# TSAL_contactor_state_and_accumulator_vol.net
KiCad netlist of a schematic drawn in EAGLE
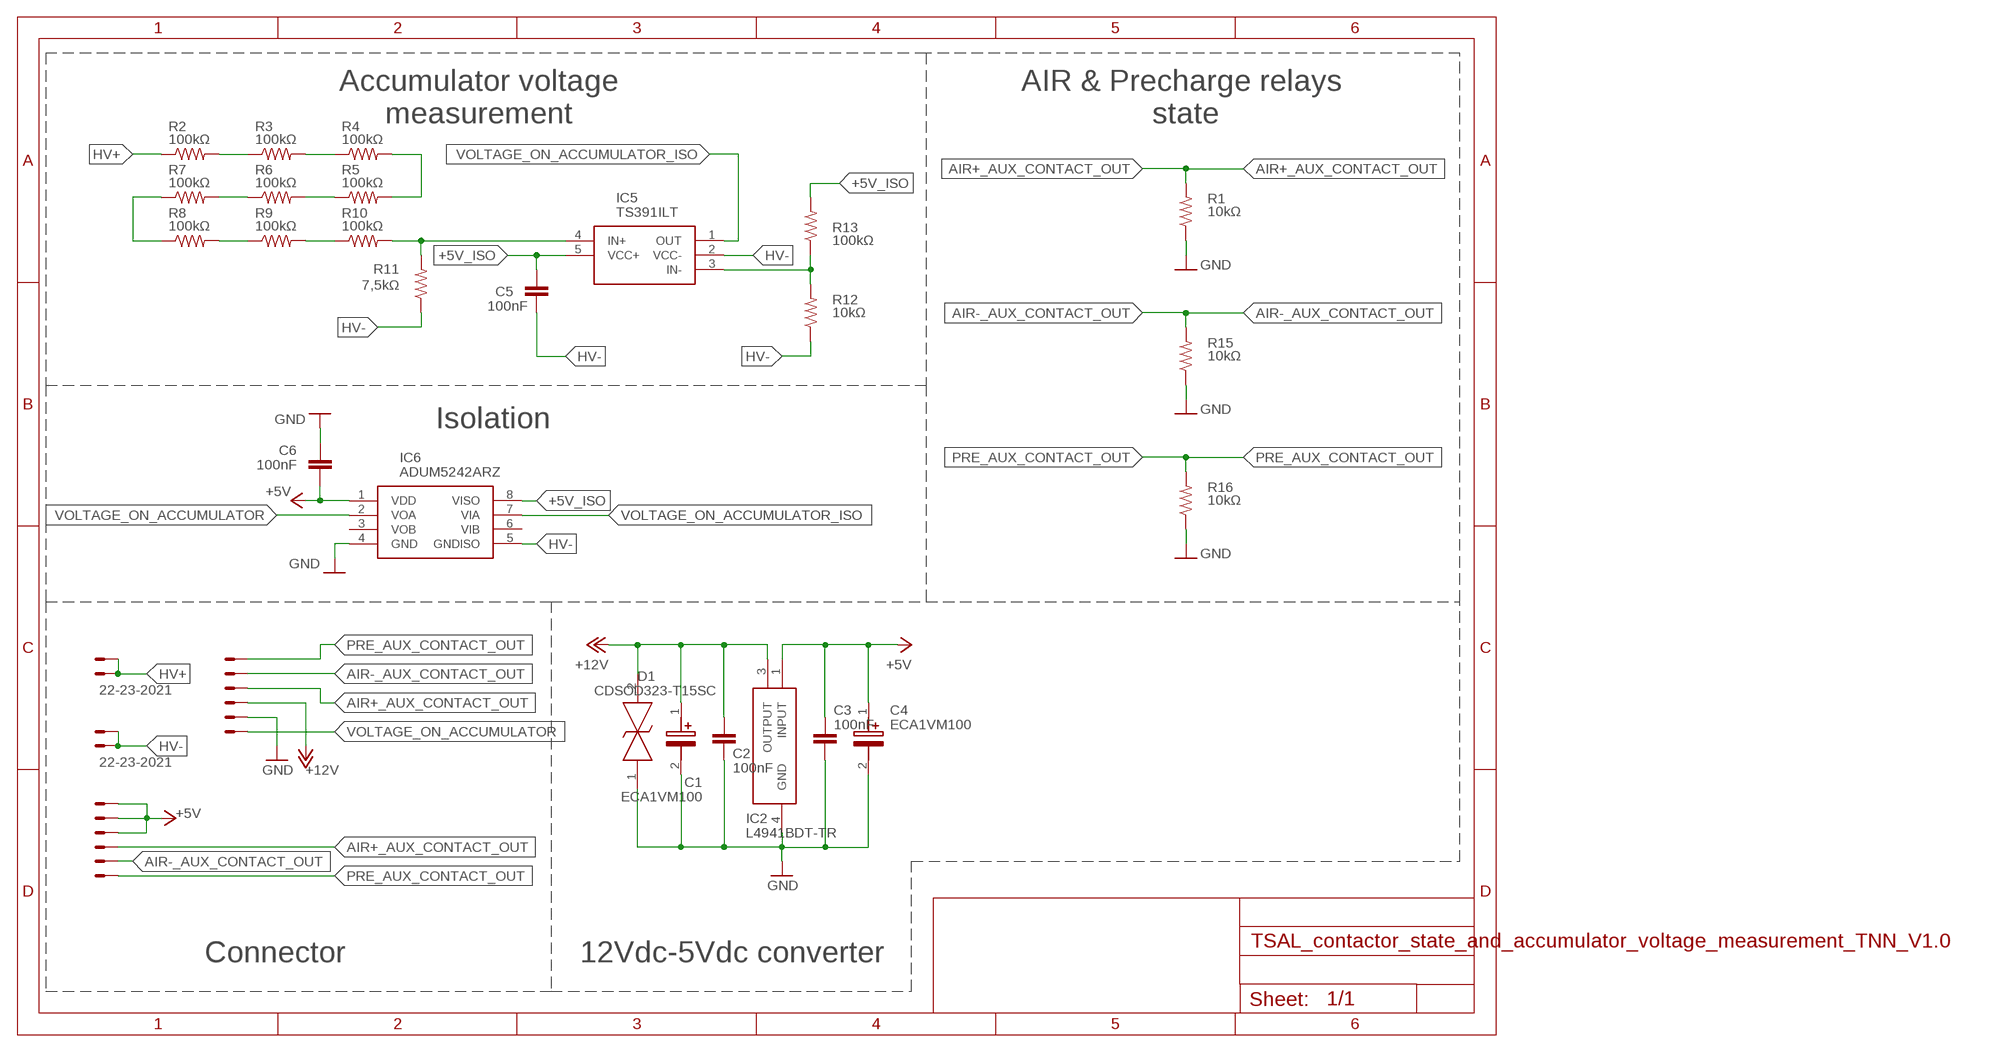
[diagram p0: schematic, sheet 1]

(export (version "E")
  (design (tool "Eeschema 10.0.6"))
  (components
    (comp (ref "AUX_CONTACT")
      (value "22-23-2061")
      (footprint "eagle-import:22-23-2061")
      (fields (field (name "MF") "MOLEX"))
      (libsource (lib "eagle-import") (part "22-23-2061"))
    )
    (comp (ref "C1")
      (value "ECA1VM100")
      (footprint "eagle-import:CAPPRD200W55D525H1200")
      (libsource (lib "eagle-import") (part "ECA1VM100"))
    )
    (comp (ref "C2")
      (value "100nF")
      (footprint "eagle-import:C0603")
      (libsource (lib "eagle-import") (part "C-EUC0603"))
    )
    (comp (ref "C3")
      (value "100nF")
      (footprint "eagle-import:C0603")
      (libsource (lib "eagle-import") (part "C-EUC0603"))
    )
    (comp (ref "C4")
      (value "ECA1VM100")
      (footprint "eagle-import:CAPPRD200W55D525H1200")
      (libsource (lib "eagle-import") (part "ECA1VM100"))
    )
    (comp (ref "C5")
      (value "100nF")
      (footprint "eagle-import:C0603")
      (libsource (lib "eagle-import") (part "C-EUC0603"))
    )
    (comp (ref "C6")
      (value "100nF")
      (footprint "eagle-import:C0603")
      (libsource (lib "eagle-import") (part "C-EUC0603"))
    )
    (comp (ref "D1")
      (value "CDSOD323-T15SC")
      (footprint "eagle-import:SOD-323")
      (fields (field (name "MOUSER_PART_NUMBER") "652-CDSOD323-T15SC"))
      (libsource (lib "eagle-import") (part "CDSOD323-T15SC"))
    )
    (comp (ref "HV+")
      (value "22-23-2021")
      (footprint "eagle-import:22-23-2021")
      (fields (field (name "MF") "MOLEX"))
      (libsource (lib "eagle-import") (part "22-23-2021"))
    )
    (comp (ref "HV-")
      (value "22-23-2021")
      (footprint "eagle-import:22-23-2021")
      (fields (field (name "MF") "MOLEX"))
      (libsource (lib "eagle-import") (part "22-23-2021"))
    )
    (comp (ref "IC2")
      (value "L4941BDT-TR")
      (footprint "eagle-import:TO228P972X240-3N")
      (fields (field (name "MOUSER_PART_NUMBER") "511-L4941BDT-TR"))
      (libsource (lib "eagle-import") (part "L4941BDT-TR"))
    )
    (comp (ref "IC5")
      (value "TS391ILT")
      (footprint "eagle-import:SOT95P280X145-5N")
      (fields (field (name "MOUSER_PART_NUMBER") "511-TS391IL"))
      (libsource (lib "eagle-import") (part "TS391ILT"))
    )
    (comp (ref "IC6")
      (value "ADUM5242ARZ")
      (footprint "eagle-import:SOIC127P600X175-8N")
      (fields (field (name "MOUSER_PART_NUMBER") "584-ADUM5242ARZ"))
      (libsource (lib "eagle-import") (part "ADUM5242ARZ"))
    )
    (comp (ref "POWER_AND_TSAL_SIGNAL")
      (value "22-23-2061")
      (footprint "eagle-import:22-23-2061")
      (fields (field (name "MF") "MOLEX"))
      (libsource (lib "eagle-import") (part "22-23-2061"))
    )
    (comp (ref "R1")
      (value "10kΩ")
      (footprint "eagle-import:R0603")
      (libsource (lib "eagle-import") (part "R-US_R0603"))
    )
    (comp (ref "R2")
      (value "100kΩ")
      (footprint "eagle-import:R0603")
      (libsource (lib "eagle-import") (part "R-US_R0603"))
    )
    (comp (ref "R3")
      (value "100kΩ")
      (footprint "eagle-import:R0603")
      (libsource (lib "eagle-import") (part "R-US_R0603"))
    )
    (comp (ref "R4")
      (value "100kΩ")
      (footprint "eagle-import:R0603")
      (libsource (lib "eagle-import") (part "R-US_R0603"))
    )
    (comp (ref "R5")
      (value "100kΩ")
      (footprint "eagle-import:R0603")
      (libsource (lib "eagle-import") (part "R-US_R0603"))
    )
    (comp (ref "R6")
      (value "100kΩ")
      (footprint "eagle-import:R0603")
      (libsource (lib "eagle-import") (part "R-US_R0603"))
    )
    (comp (ref "R7")
      (value "100kΩ")
      (footprint "eagle-import:R0603")
      (libsource (lib "eagle-import") (part "R-US_R0603"))
    )
    (comp (ref "R8")
      (value "100kΩ")
      (footprint "eagle-import:R0603")
      (libsource (lib "eagle-import") (part "R-US_R0603"))
    )
    (comp (ref "R9")
      (value "100kΩ")
      (footprint "eagle-import:R0603")
      (libsource (lib "eagle-import") (part "R-US_R0603"))
    )
    (comp (ref "R10")
      (value "100kΩ")
      (footprint "eagle-import:R0603")
      (libsource (lib "eagle-import") (part "R-US_R0603"))
    )
    (comp (ref "R11")
      (value "7,5kΩ")
      (footprint "eagle-import:R0603")
      (libsource (lib "eagle-import") (part "R-US_R0603"))
    )
    (comp (ref "R12")
      (value "10kΩ")
      (footprint "eagle-import:R0603")
      (libsource (lib "eagle-import") (part "R-US_R0603"))
    )
    (comp (ref "R13")
      (value "100kΩ")
      (footprint "eagle-import:R0603")
      (libsource (lib "eagle-import") (part "R-US_R0603"))
    )
    (comp (ref "R15")
      (value "10kΩ")
      (footprint "eagle-import:R0603")
      (libsource (lib "eagle-import") (part "R-US_R0603"))
    )
    (comp (ref "R16")
      (value "10kΩ")
      (footprint "eagle-import:R0603")
      (libsource (lib "eagle-import") (part "R-US_R0603"))
    )
  )
  (nets
    (net (code "1") (name "+5V") (class "Default")
      (node (ref "AUX_CONTACT") (pin "4") (pinfunction "S_4") (pintype "passive"))
      (node (ref "AUX_CONTACT") (pin "5") (pinfunction "S_5") (pintype "passive"))
      (node (ref "AUX_CONTACT") (pin "6") (pinfunction "S_6") (pintype "passive"))
      (node (ref "C3") (pin "1") (pinfunction "1_1") (pintype "passive"))
      (node (ref "C4") (pin "1") (pinfunction "+_1") (pintype "bidirectional"))
      (node (ref "C6") (pin "1") (pinfunction "1_1") (pintype "passive"))
      (node (ref "IC2") (pin "1") (pinfunction "INPUT_1") (pintype "output"))
      (node (ref "IC6") (pin "1") (pinfunction "VDD_1") (pintype "bidirectional"))
    )
    (net (code "2") (name "+5V_ISO") (class "Default")
      (node (ref "C5") (pin "2") (pinfunction "2_2") (pintype "passive"))
      (node (ref "IC5") (pin "5") (pinfunction "VCC+_5") (pintype "bidirectional"))
      (node (ref "IC6") (pin "8") (pinfunction "VISO_8") (pintype "bidirectional"))
      (node (ref "R13") (pin "2") (pinfunction "2_2") (pintype "passive"))
    )
    (net (code "3") (name "+12V") (class "Default")
      (node (ref "C1") (pin "1") (pinfunction "+_1") (pintype "bidirectional"))
      (node (ref "C2") (pin "1") (pinfunction "1_1") (pintype "passive"))
      (node (ref "D1") (pin "2") (pinfunction "2_2") (pintype "bidirectional"))
      (node (ref "IC2") (pin "3") (pinfunction "OUTPUT_3") (pintype "power_in"))
      (node (ref "POWER_AND_TSAL_SIGNAL") (pin "3") (pinfunction "S_3") (pintype "passive"))
    )
    (net (code "4") (name "AIR+_AUX_CONTACT_OUT") (class "Default")
      (node (ref "AUX_CONTACT") (pin "3") (pinfunction "S_3") (pintype "passive"))
      (node (ref "POWER_AND_TSAL_SIGNAL") (pin "4") (pinfunction "S_4") (pintype "passive"))
      (node (ref "R1") (pin "2") (pinfunction "2_2") (pintype "passive"))
    )
    (net (code "5") (name "AIR-_AUX_CONTACT_OUT") (class "Default")
      (node (ref "AUX_CONTACT") (pin "2") (pinfunction "S_2") (pintype "passive"))
      (node (ref "POWER_AND_TSAL_SIGNAL") (pin "5") (pinfunction "S_5") (pintype "passive"))
      (node (ref "R15") (pin "2") (pinfunction "2_2") (pintype "passive"))
    )
    (net (code "6") (name "GND") (class "Default")
      (node (ref "C1") (pin "2") (pinfunction "-_2") (pintype "bidirectional"))
      (node (ref "C2") (pin "2") (pinfunction "2_2") (pintype "passive"))
      (node (ref "C3") (pin "2") (pinfunction "2_2") (pintype "passive"))
      (node (ref "C4") (pin "2") (pinfunction "-_2") (pintype "bidirectional"))
      (node (ref "C6") (pin "2") (pinfunction "2_2") (pintype "passive"))
      (node (ref "D1") (pin "1") (pinfunction "1_1") (pintype "bidirectional"))
      (node (ref "IC2") (pin "4") (pinfunction "GND_4") (pintype "input"))
      (node (ref "IC6") (pin "4") (pinfunction "GND_4") (pintype "bidirectional"))
      (node (ref "POWER_AND_TSAL_SIGNAL") (pin "2") (pinfunction "S_2") (pintype "passive"))
      (node (ref "R1") (pin "1") (pinfunction "1_1") (pintype "passive"))
      (node (ref "R15") (pin "1") (pinfunction "1_1") (pintype "passive"))
      (node (ref "R16") (pin "1") (pinfunction "1_1") (pintype "passive"))
    )
    (net (code "7") (name "HV+") (class "Default")
      (node (ref "HV+") (pin "1") (pinfunction "S_1") (pintype "passive"))
      (node (ref "HV+") (pin "2") (pinfunction "S_2") (pintype "passive"))
      (node (ref "R2") (pin "1") (pinfunction "1_1") (pintype "passive"))
    )
    (net (code "8") (name "HV-") (class "Default")
      (node (ref "C5") (pin "1") (pinfunction "1_1") (pintype "passive"))
      (node (ref "HV-") (pin "1") (pinfunction "S_1") (pintype "passive"))
      (node (ref "HV-") (pin "2") (pinfunction "S_2") (pintype "passive"))
      (node (ref "IC5") (pin "2") (pinfunction "VCC-_2") (pintype "bidirectional"))
      (node (ref "IC6") (pin "5") (pinfunction "GNDISO_5") (pintype "bidirectional"))
      (node (ref "R11") (pin "1") (pinfunction "1_1") (pintype "passive"))
      (node (ref "R12") (pin "1") (pinfunction "1_1") (pintype "passive"))
    )
    (net (code "9") (name "Net-(IC5-IN+)") (class "Default")
      (node (ref "IC5") (pin "4") (pinfunction "IN+_4") (pintype "bidirectional"))
      (node (ref "R10") (pin "2") (pinfunction "2_2") (pintype "passive"))
      (node (ref "R11") (pin "2") (pinfunction "2_2") (pintype "passive"))
    )
    (net (code "10") (name "Net-(IC5-IN-)") (class "Default")
      (node (ref "IC5") (pin "3") (pinfunction "IN-_3") (pintype "bidirectional"))
      (node (ref "R12") (pin "2") (pinfunction "2_2") (pintype "passive"))
      (node (ref "R13") (pin "1") (pinfunction "1_1") (pintype "passive"))
    )
    (net (code "11") (name "Net-(R2-Pad2)") (class "Default")
      (node (ref "R2") (pin "2") (pinfunction "2_2") (pintype "passive"))
      (node (ref "R3") (pin "1") (pinfunction "1_1") (pintype "passive"))
    )
    (net (code "12") (name "Net-(R3-Pad2)") (class "Default")
      (node (ref "R3") (pin "2") (pinfunction "2_2") (pintype "passive"))
      (node (ref "R4") (pin "1") (pinfunction "1_1") (pintype "passive"))
    )
    (net (code "13") (name "Net-(R4-Pad2)") (class "Default")
      (node (ref "R4") (pin "2") (pinfunction "2_2") (pintype "passive"))
      (node (ref "R5") (pin "2") (pinfunction "2_2") (pintype "passive"))
    )
    (net (code "14") (name "Net-(R5-Pad1)") (class "Default")
      (node (ref "R5") (pin "1") (pinfunction "1_1") (pintype "passive"))
      (node (ref "R6") (pin "2") (pinfunction "2_2") (pintype "passive"))
    )
    (net (code "15") (name "Net-(R6-Pad1)") (class "Default")
      (node (ref "R6") (pin "1") (pinfunction "1_1") (pintype "passive"))
      (node (ref "R7") (pin "2") (pinfunction "2_2") (pintype "passive"))
    )
    (net (code "16") (name "Net-(R7-Pad1)") (class "Default")
      (node (ref "R7") (pin "1") (pinfunction "1_1") (pintype "passive"))
      (node (ref "R8") (pin "1") (pinfunction "1_1") (pintype "passive"))
    )
    (net (code "17") (name "Net-(R8-Pad2)") (class "Default")
      (node (ref "R8") (pin "2") (pinfunction "2_2") (pintype "passive"))
      (node (ref "R9") (pin "1") (pinfunction "1_1") (pintype "passive"))
    )
    (net (code "18") (name "Net-(R10-Pad1)") (class "Default")
      (node (ref "R10") (pin "1") (pinfunction "1_1") (pintype "passive"))
      (node (ref "R9") (pin "2") (pinfunction "2_2") (pintype "passive"))
    )
    (net (code "19") (name "PRE_AUX_CONTACT_OUT") (class "Default")
      (node (ref "AUX_CONTACT") (pin "1") (pinfunction "S_1") (pintype "passive"))
      (node (ref "POWER_AND_TSAL_SIGNAL") (pin "6") (pinfunction "S_6") (pintype "passive"))
      (node (ref "R16") (pin "2") (pinfunction "2_2") (pintype "passive"))
    )
    (net (code "20") (name "VOLTAGE_ON_ACCUMULATOR") (class "Default")
      (node (ref "IC6") (pin "2") (pinfunction "VOA_2") (pintype "bidirectional"))
      (node (ref "POWER_AND_TSAL_SIGNAL") (pin "1") (pinfunction "S_1") (pintype "passive"))
    )
    (net (code "21") (name "VOLTAGE_ON_ACCUMULATOR_ISO") (class "Default")
      (node (ref "IC5") (pin "1") (pinfunction "OUT_1") (pintype "bidirectional"))
      (node (ref "IC6") (pin "7") (pinfunction "VIA_7") (pintype "bidirectional"))
    )
    (net (code "22") (name "unconnected-(IC6-VIB-Pad6)") (class "Default")
      (node (ref "IC6") (pin "6") (pinfunction "VIB_6") (pintype "bidirectional"))
    )
    (net (code "23") (name "unconnected-(IC6-VOB-Pad3)") (class "Default")
      (node (ref "IC6") (pin "3") (pinfunction "VOB_3") (pintype "bidirectional"))
    )
  )
)
